# Interconnect.net
KiCad netlist of a schematic drawn in Altium Designer
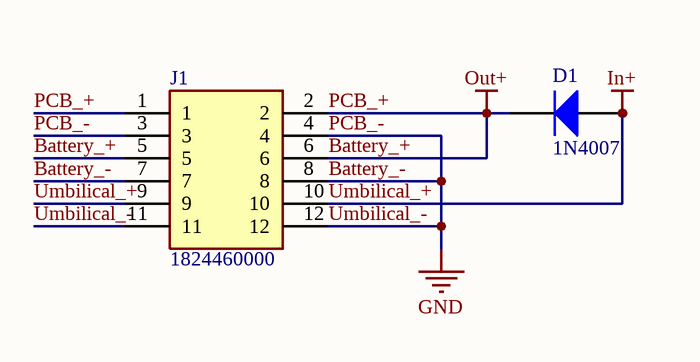
[diagram p0: Interconnect.SchDoc]

(export (version "E")
  (design (tool "Eeschema 10.0.6"))
  (components
    (comp (ref "D1")
      (value "1N4007")
      (footprint "FAIR-DO-41-2")
      (description "General Purpose Rectifier, 1.1 V, 1.0 A, -55 to 175 degC, 2-Pin DO-41, RoHS, Tape and Reel")
      (fields (field (name "MANUFACTURER") "Fairchild"))
      (libsource (lib "StrathSEDS") (part "KESE-D_K1A2-2"))
    )
    (comp (ref "J1")
      (value "1824460000")
      (footprint "SHDR12W80P700X350_2X6_2170X1400X850P")
      (fields (field (name "MOUSER PART NUMBER") "470-1824460000"))
      (libsource (lib "StrathSEDS") (part "1824460000"))
    )
  )
  (nets
    (net (code "1") (name "GND") (class "Default")
      (node (ref "J1") (pin "11") (pinfunction "11_11") (pintype "passive"))
      (node (ref "J1") (pin "12") (pinfunction "12_12") (pintype "passive"))
      (node (ref "J1") (pin "3") (pinfunction "3_3") (pintype "passive"))
      (node (ref "J1") (pin "4") (pinfunction "4_4") (pintype "passive"))
      (node (ref "J1") (pin "7") (pinfunction "7_7") (pintype "passive"))
      (node (ref "J1") (pin "8") (pinfunction "8_8") (pintype "passive"))
    )
    (net (code "2") (name "In+") (class "Default")
      (node (ref "D1") (pin "2") (pinfunction "A_2") (pintype "passive"))
      (node (ref "J1") (pin "10") (pinfunction "10_10") (pintype "passive"))
      (node (ref "J1") (pin "9") (pinfunction "9_9") (pintype "passive"))
    )
    (net (code "3") (name "Out+") (class "Default")
      (node (ref "D1") (pin "1") (pinfunction "K_1") (pintype "passive"))
      (node (ref "J1") (pin "1") (pinfunction "1_1") (pintype "passive"))
      (node (ref "J1") (pin "2") (pinfunction "2_2") (pintype "passive"))
      (node (ref "J1") (pin "5") (pinfunction "5_5") (pintype "passive"))
      (node (ref "J1") (pin "6") (pinfunction "6_6") (pintype "passive"))
    )
  )
)
